# PRJCTSheet1.net
KiCad netlist of a schematic drawn in Altium Designer
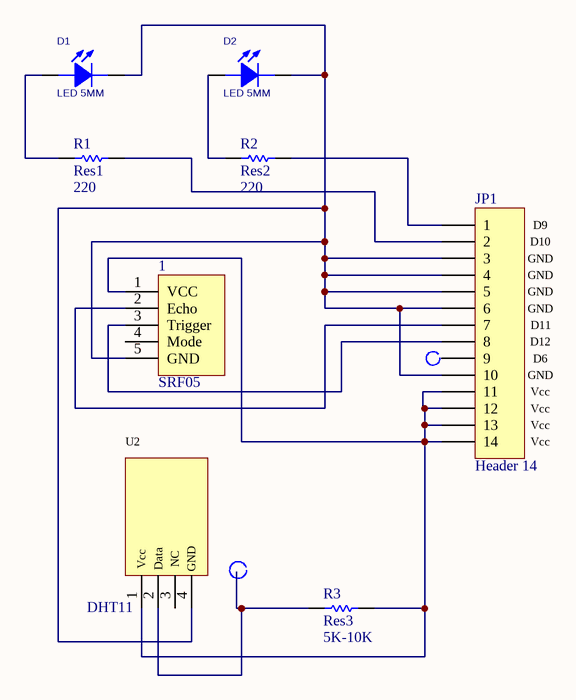
[diagram p0: PRJCTSheet1.SchDoc]

(export (version "E")
  (design (tool "Eeschema 10.0.6"))
  (components
    (comp (ref "1")
      (value "SRF05")
      (footprint "SRF05")
      (description "SRF05 - Ultra-Sonic Ranger")
      (fields (field (name "DESIGNER") "Seyed Mohsen ghasemian"))
      (libsource (lib "PicPars.com_usefully_Library") (part "SRF05"))
    )
    (comp (ref "D1")
      (value "LED 5MM")
      (footprint "LED5MM_BLUE")
      (description "Light Emitting Diode")
      (fields (field (name "DESIGNER") "Abbas Basereh"))
      (libsource (lib "Altium") (part "LED 5MM"))
    )
    (comp (ref "D2")
      (value "LED 5MM")
      (footprint "LED5MM_BLUE")
      (description "Light Emitting Diode")
      (fields (field (name "DESIGNER") "Abbas Basereh"))
      (libsource (lib "Altium") (part "LED 5MM"))
    )
    (comp (ref "JP1")
      (value "Header 14")
      (footprint "HDR1X14")
      (description "Header, 14-Pin")
      (fields (field (name "PUBLISHER") "Altium Limited"))
      (libsource (lib "Miscellaneous Connectors") (part "Header 14"))
    )
    (comp (ref "R1")
      (value "Res1")
      (footprint "AXIAL-0.3")
      (description "Resistor")
      (fields (field (name "ALTIUM_VALUE") "220") (field (name "PUBLISHER") "Altium Limited"))
      (libsource (lib "Miscellaneous Devices") (part "Res1"))
    )
    (comp (ref "R2")
      (value "Res2")
      (footprint "AXIAL-0.3")
      (description "Resistor")
      (fields (field (name "ALTIUM_VALUE") "220") (field (name "PUBLISHER") "Altium Limited"))
      (libsource (lib "Miscellaneous Devices") (part "Res1"))
    )
    (comp (ref "R3")
      (value "Res3")
      (footprint "AXIAL-0.3")
      (description "Resistor")
      (fields (field (name "ALTIUM_VALUE") "5K-10K") (field (name "PUBLISHER") "Altium Limited"))
      (libsource (lib "Miscellaneous Devices") (part "Res1"))
    )
    (comp (ref "U1") (value "DHT11") (footprint "DHT11") (libsource (lib "DHT11") (part "DHT11")))
  )
  (nets
    (net (code "1") (name "Net-(1-Echo)") (class "Default")
      (node (ref "1") (pin "2") (pinfunction "Echo_2") (pintype "passive"))
      (node (ref "JP1") (pin "7") (pinfunction "7_7") (pintype "passive"))
    )
    (net (code "2") (name "Net-(1-GND)") (class "Default")
      (node (ref "1") (pin "5") (pinfunction "GND_5") (pintype "passive"))
      (node (ref "D1") (pin "2") (pinfunction "CATHODE_2") (pintype "passive"))
      (node (ref "D2") (pin "2") (pinfunction "CATHODE_2") (pintype "passive"))
      (node (ref "JP1") (pin "10") (pinfunction "10_10") (pintype "passive"))
      (node (ref "JP1") (pin "3") (pinfunction "3_3") (pintype "passive"))
      (node (ref "JP1") (pin "4") (pinfunction "4_4") (pintype "passive"))
      (node (ref "JP1") (pin "5") (pinfunction "5_5") (pintype "passive"))
      (node (ref "JP1") (pin "6") (pinfunction "6_6") (pintype "passive"))
      (node (ref "U1") (pin "4") (pinfunction "4_4") (pintype "passive"))
    )
    (net (code "3") (name "Net-(1-Trigger)") (class "Default")
      (node (ref "1") (pin "3") (pinfunction "Trigger_3") (pintype "passive"))
      (node (ref "JP1") (pin "8") (pinfunction "8_8") (pintype "passive"))
    )
    (net (code "4") (name "Net-(1-VCC)") (class "Default")
      (node (ref "1") (pin "1") (pinfunction "VCC_1") (pintype "passive"))
      (node (ref "JP1") (pin "11") (pinfunction "11_11") (pintype "passive"))
      (node (ref "JP1") (pin "12") (pinfunction "12_12") (pintype "passive"))
      (node (ref "JP1") (pin "13") (pinfunction "13_13") (pintype "passive"))
      (node (ref "JP1") (pin "14") (pinfunction "14_14") (pintype "passive"))
      (node (ref "R3") (pin "2") (pinfunction "2_2") (pintype "passive"))
      (node (ref "U1") (pin "1") (pinfunction "1_1") (pintype "passive"))
    )
    (net (code "5") (name "Net-(D1-ANODE)") (class "Default")
      (node (ref "D1") (pin "1") (pinfunction "ANODE_1") (pintype "passive"))
      (node (ref "R1") (pin "1") (pinfunction "1_1") (pintype "passive"))
    )
    (net (code "6") (name "Net-(D2-ANODE)") (class "Default")
      (node (ref "D2") (pin "1") (pinfunction "ANODE_1") (pintype "passive"))
      (node (ref "R2") (pin "1") (pinfunction "1_1") (pintype "passive"))
    )
    (net (code "7") (name "Net-(JP1-Pad1)") (class "Default")
      (node (ref "JP1") (pin "1") (pinfunction "1_1") (pintype "passive"))
      (node (ref "R2") (pin "2") (pinfunction "2_2") (pintype "passive"))
    )
    (net (code "8") (name "Net-(JP1-Pad2)") (class "Default")
      (node (ref "JP1") (pin "2") (pinfunction "2_2") (pintype "passive"))
      (node (ref "R1") (pin "2") (pinfunction "2_2") (pintype "passive"))
    )
    (net (code "9") (name "Net-(R3-Pad1)") (class "Default")
      (node (ref "R3") (pin "1") (pinfunction "1_1") (pintype "passive"))
      (node (ref "U1") (pin "2") (pinfunction "2_2") (pintype "passive"))
    )
    (net (code "10") (name "unconnected-(1-Mode-Pad4)") (class "Default")
      (node (ref "1") (pin "4") (pinfunction "Mode_4") (pintype "passive"))
    )
    (net (code "11") (name "unconnected-(JP1-Pad9)") (class "Default")
      (node (ref "JP1") (pin "9") (pinfunction "9_9") (pintype "passive"))
    )
    (net (code "12") (name "unconnected-(U1-Pad3)") (class "Default")
      (node (ref "U1") (pin "3") (pinfunction "3_3") (pintype "passive"))
    )
  )
)
